# 5VBuck_MP2315S_P1.net
KiCad netlist of a schematic drawn in EasyEDA Pro
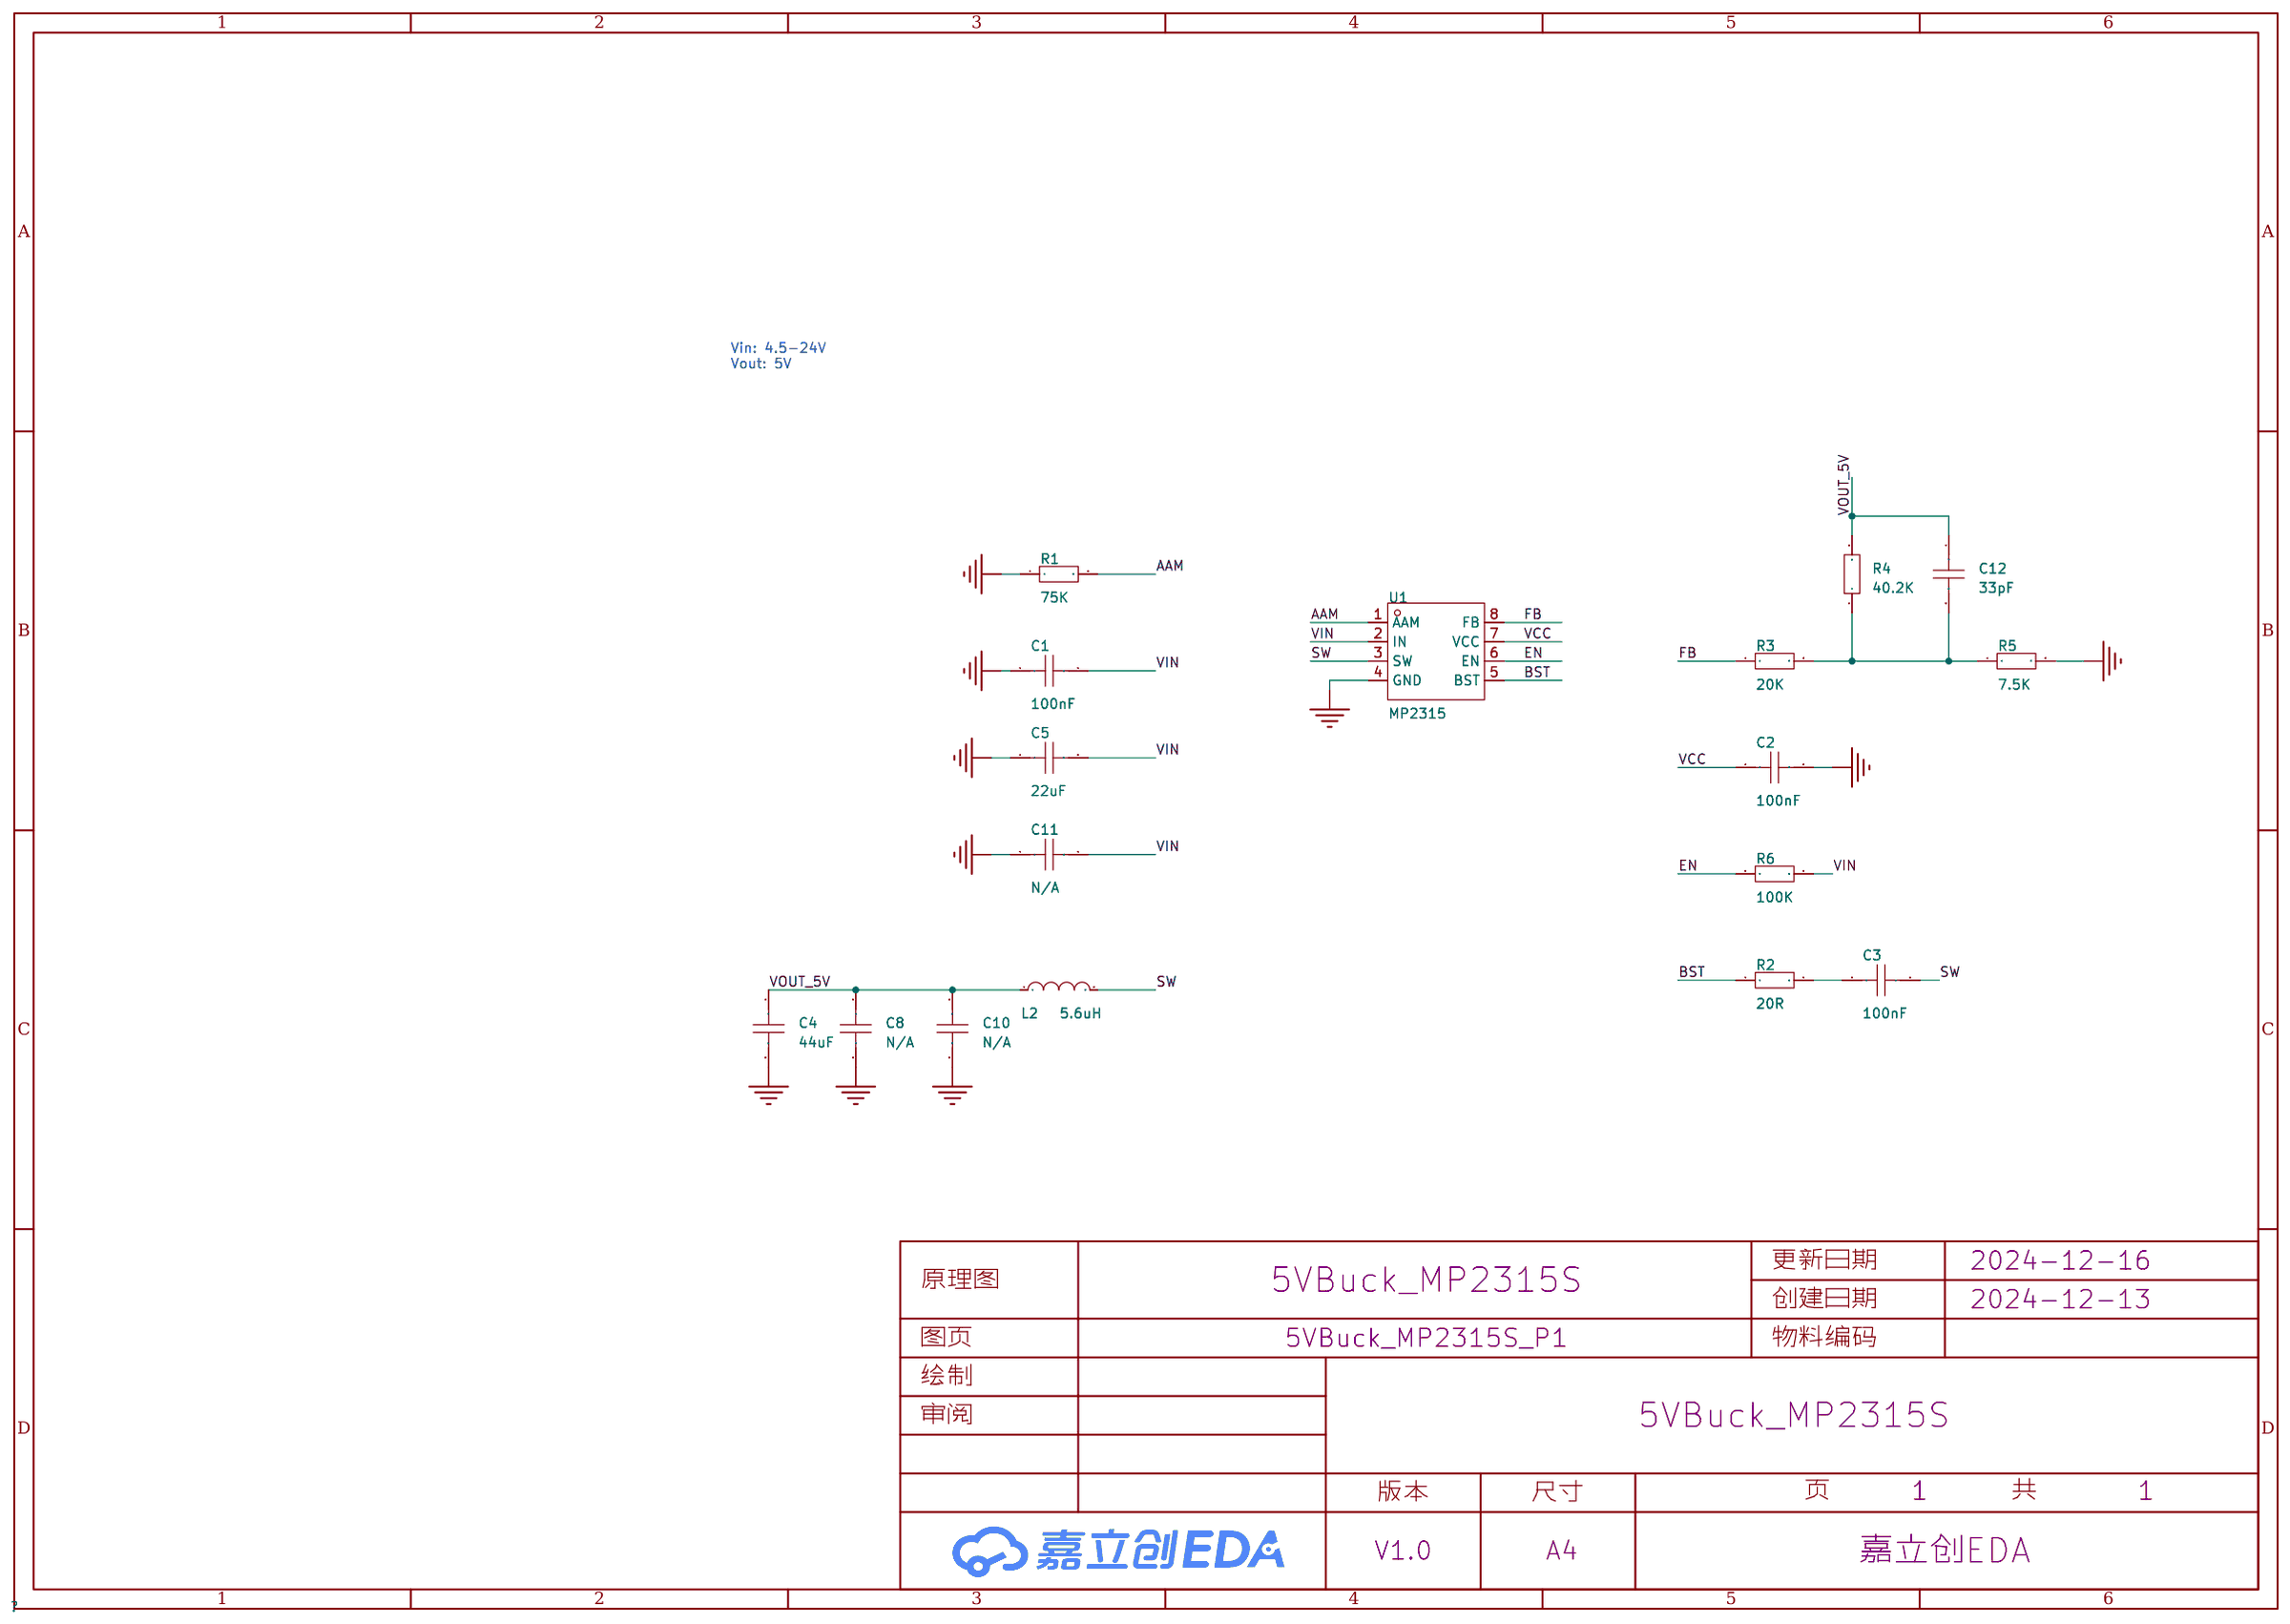
[diagram p0: schematic sheet]

(export (version "E")
  (design (tool "Eeschema 10.0.6"))
  (components
    (comp (ref "C1")
      (value "100nF")
      (footprint "easyedapro:C0805")
      (libsource (lib "easyedapro") (part "CapAcitance"))
    )
    (comp (ref "C2")
      (value "100nF")
      (footprint "easyedapro:C0805")
      (libsource (lib "easyedapro") (part "CapAcitance"))
    )
    (comp (ref "C3")
      (value "100nF")
      (footprint "easyedapro:C0805")
      (libsource (lib "easyedapro") (part "CapAcitance"))
    )
    (comp (ref "C4")
      (value "44uF")
      (footprint "easyedapro:C0805")
      (libsource (lib "easyedapro") (part "CapAcitance"))
    )
    (comp (ref "C5")
      (value "22uF")
      (footprint "easyedapro:C0805")
      (libsource (lib "easyedapro") (part "CapAcitance"))
    )
    (comp (ref "C8")
      (value "100nF")
      (footprint "easyedapro:C0805")
      (libsource (lib "easyedapro") (part "CapAcitance"))
    )
    (comp (ref "C10")
      (value "N/A")
      (footprint "easyedapro:C0805")
      (libsource (lib "easyedapro") (part "CapAcitance"))
    )
    (comp (ref "C11")
      (value "N/A")
      (footprint "easyedapro:C0805")
      (libsource (lib "easyedapro") (part "CapAcitance"))
    )
    (comp (ref "C12")
      (value "33pF")
      (footprint "easyedapro:C0805")
      (libsource (lib "easyedapro") (part "CapAcitance"))
    )
    (comp (ref "L2")
      (value "5.6uH")
      (footprint "easyedapro:IND-SMD_L7.1-W6.6_MJC-0603T")
      (description "电感值:5.6uH;精度:±20%;额定电流:5.5A;饱和电流(Isat):7A;类型:一体成型电感;")
      (fields
        (field (name "Manufacturer Part") "CXP0630-5R6M-AG(5.6uh)")
        (field (name "Manufacturer") "DMBJ(振宝佳)")
      )
      (libsource (lib "easyedapro") (part "CXP0630-5R6M-AG(5.6UH)"))
    )
    (comp (ref "R1") (value "75K") (footprint "easyedapro:R0805") (libsource (lib "easyedapro") (part "电阻")))
    (comp (ref "R2") (value "20R") (footprint "easyedapro:R0805") (libsource (lib "easyedapro") (part "电阻")))
    (comp (ref "R3") (value "20K") (footprint "easyedapro:R0805") (libsource (lib "easyedapro") (part "电阻")))
    (comp (ref "R4")
      (value "40.2K")
      (footprint "easyedapro:R0805")
      (libsource (lib "easyedapro") (part "电阻"))
    )
    (comp (ref "R5") (value "7.5K") (footprint "easyedapro:R0805") (libsource (lib "easyedapro") (part "电阻")))
    (comp (ref "R6") (value "100K") (footprint "easyedapro:R0805") (libsource (lib "easyedapro") (part "电阻")))
    (comp (ref "U1")
      (value "MP2315")
      (footprint "easyedapro:SOT-23-8_L2.9-W1.6-P0.65-LS2.8-BL")
      (libsource (lib "easyedapro") (part "MP2315"))
    )
  )
  (nets
    (net (code "1") (name "/AAM") (class "Default")
      (node (ref "R1") (pin "2") (pinfunction "2_2") (pintype "input"))
      (node (ref "U1") (pin "1") (pinfunction "AAM_1") (pintype "unspecified"))
    )
    (net (code "2") (name "/BST") (class "Default")
      (node (ref "R2") (pin "1") (pinfunction "1_1") (pintype "input"))
      (node (ref "U1") (pin "5") (pinfunction "BST_5") (pintype "unspecified"))
    )
    (net (code "3") (name "/EN") (class "Default")
      (node (ref "R6") (pin "2") (pinfunction "2_2") (pintype "input"))
      (node (ref "U1") (pin "6") (pinfunction "EN_6") (pintype "unspecified"))
    )
    (net (code "4") (name "/FB") (class "Default")
      (node (ref "R3") (pin "1") (pinfunction "1_1") (pintype "input"))
      (node (ref "U1") (pin "8") (pinfunction "FB_8") (pintype "unspecified"))
    )
    (net (code "5") (name "/SW") (class "Default")
      (node (ref "C3") (pin "2") (pinfunction "2_2") (pintype "input"))
      (node (ref "L2") (pin "2") (pinfunction "2_2") (pintype "unspecified"))
      (node (ref "U1") (pin "3") (pinfunction "SW_3") (pintype "unspecified"))
    )
    (net (code "6") (name "/VCC") (class "Default")
      (node (ref "C2") (pin "1") (pinfunction "1_1") (pintype "input"))
      (node (ref "U1") (pin "7") (pinfunction "VCC_7") (pintype "unspecified"))
    )
    (net (code "7") (name "/VIN") (class "Default")
      (node (ref "C1") (pin "2") (pinfunction "2_2") (pintype "input"))
      (node (ref "C11") (pin "2") (pinfunction "2_2") (pintype "input"))
      (node (ref "C5") (pin "2") (pinfunction "2_2") (pintype "input"))
      (node (ref "R6") (pin "1") (pinfunction "1_1") (pintype "input"))
      (node (ref "U1") (pin "2") (pinfunction "IN_2") (pintype "unspecified"))
    )
    (net (code "8") (name "/VOUT_5V") (class "Default")
      (node (ref "C10") (pin "1") (pinfunction "1_1") (pintype "input"))
      (node (ref "C12") (pin "1") (pinfunction "1_1") (pintype "input"))
      (node (ref "C4") (pin "1") (pinfunction "1_1") (pintype "input"))
      (node (ref "C8") (pin "1") (pinfunction "1_1") (pintype "input"))
      (node (ref "L2") (pin "1") (pinfunction "1_1") (pintype "unspecified"))
      (node (ref "R4") (pin "2") (pinfunction "2_2") (pintype "input"))
    )
    (net (code "9") (name "GND") (class "Default")
      (node (ref "C1") (pin "1") (pinfunction "1_1") (pintype "input"))
      (node (ref "C10") (pin "2") (pinfunction "2_2") (pintype "input"))
      (node (ref "C11") (pin "1") (pinfunction "1_1") (pintype "input"))
      (node (ref "C2") (pin "2") (pinfunction "2_2") (pintype "input"))
      (node (ref "C4") (pin "2") (pinfunction "2_2") (pintype "input"))
      (node (ref "C5") (pin "1") (pinfunction "1_1") (pintype "input"))
      (node (ref "C8") (pin "2") (pinfunction "2_2") (pintype "input"))
      (node (ref "R1") (pin "1") (pinfunction "1_1") (pintype "input"))
      (node (ref "R5") (pin "2") (pinfunction "2_2") (pintype "input"))
      (node (ref "U1") (pin "4") (pinfunction "GND_4") (pintype "unspecified"))
    )
    (net (code "10") (name "Net-(C3-Pad1)") (class "Default")
      (node (ref "C3") (pin "1") (pinfunction "1_1") (pintype "input"))
      (node (ref "R2") (pin "2") (pinfunction "2_2") (pintype "input"))
    )
    (net (code "11") (name "Net-(C12-Pad2)") (class "Default")
      (node (ref "C12") (pin "2") (pinfunction "2_2") (pintype "input"))
      (node (ref "R3") (pin "2") (pinfunction "2_2") (pintype "input"))
      (node (ref "R4") (pin "1") (pinfunction "1_1") (pintype "input"))
      (node (ref "R5") (pin "1") (pinfunction "1_1") (pintype "input"))
    )
  )
)
